# G22V5.net
KiCad netlist of a schematic drawn in EAGLE
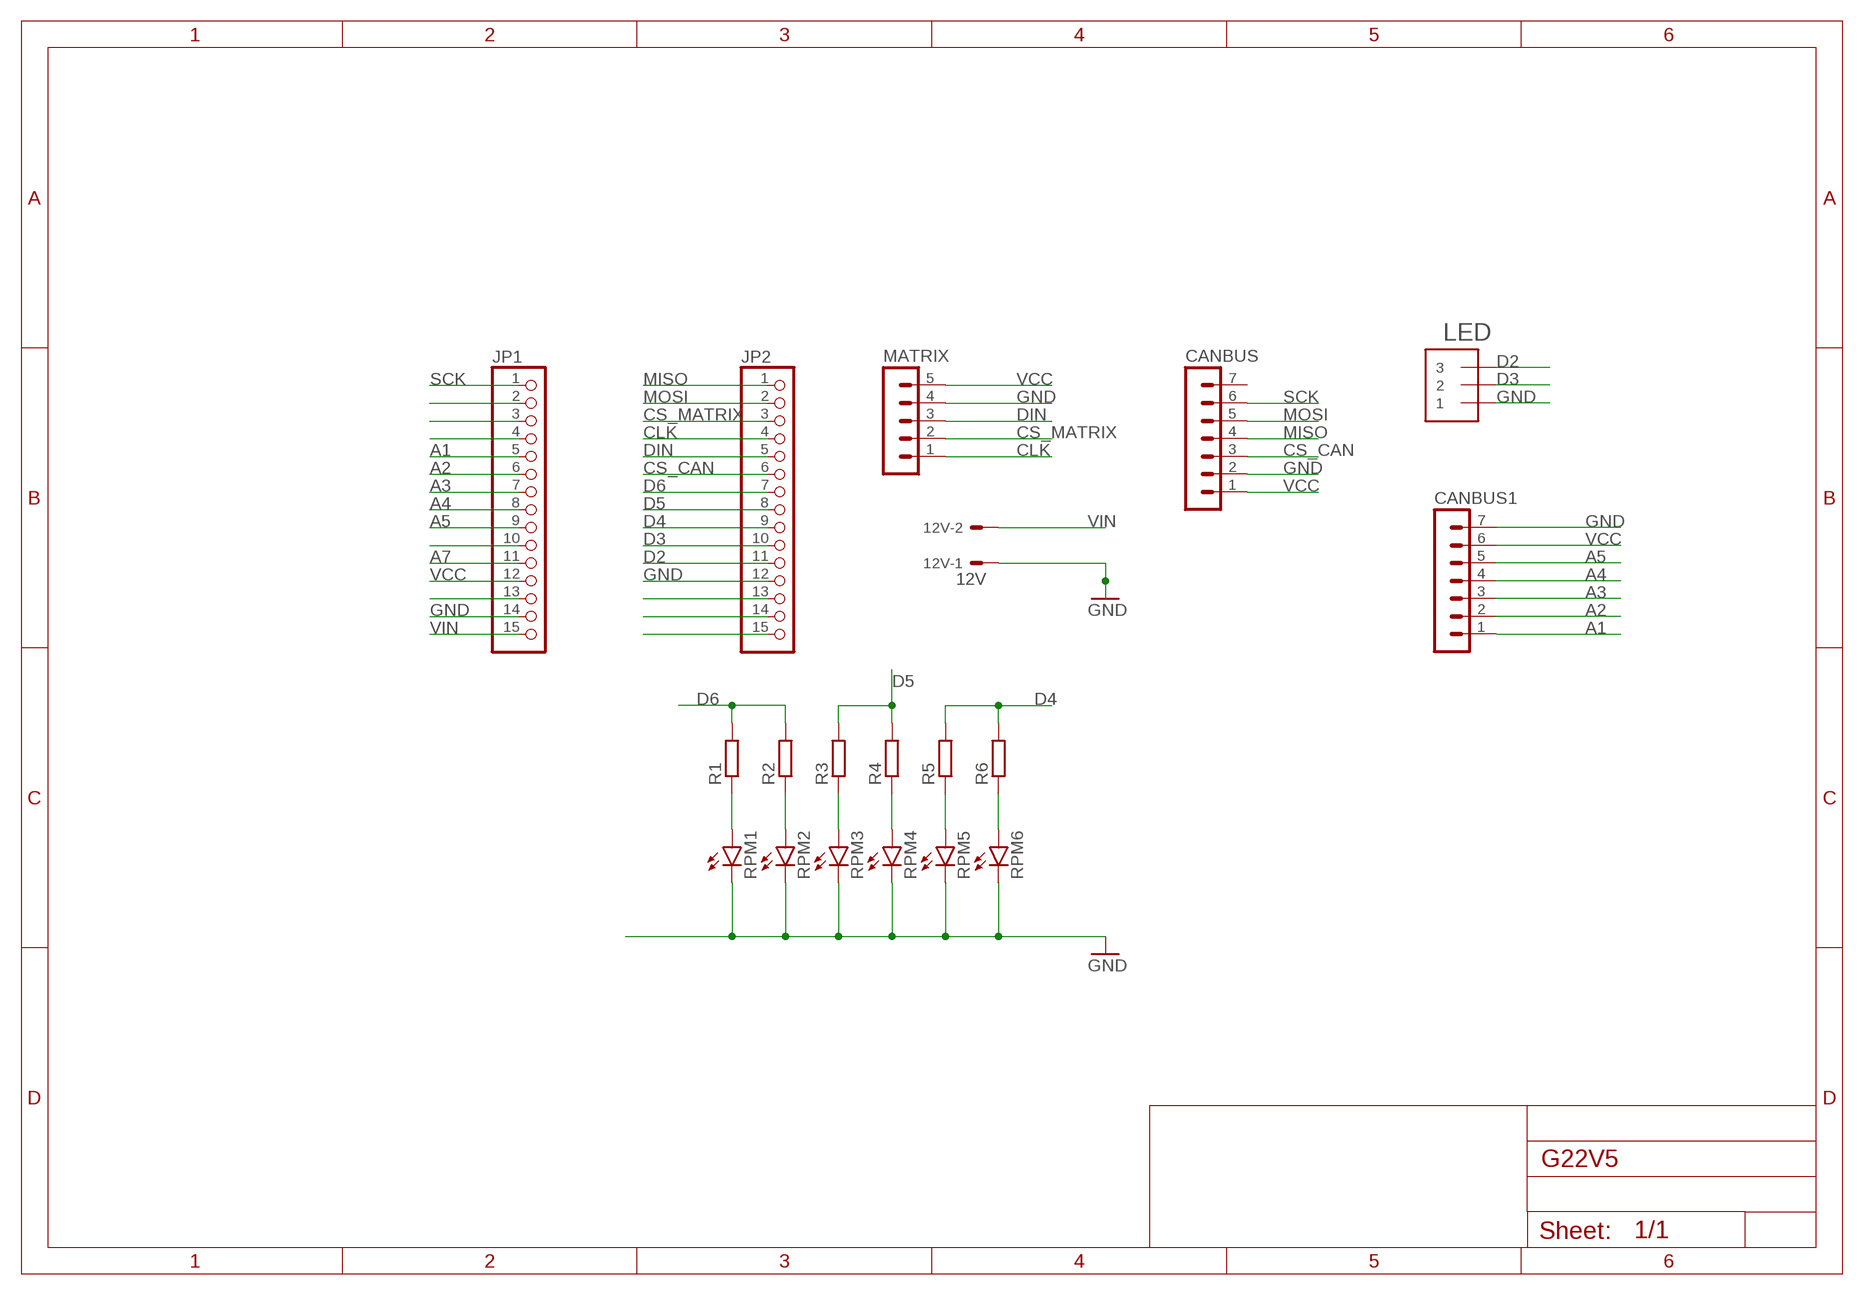
[diagram p0: schematic, sheet 1]

(export (version "E")
  (design (tool "Eeschema 10.0.6"))
  (components
    (comp (ref "12V")
      (value "12V")
      (footprint "eagle-import:22-23-2021")
      (fields (field (name "MF") "MOLEX") (field (name "MPN") "22-23-2021"))
      (libsource (lib "eagle-import") (part "22-23-2021"))
    )
    (comp (ref "CANBUS")
      (value "MA07-1")
      (footprint "eagle-import:MA07-1")
      (libsource (lib "eagle-import") (part "MA07-1"))
    )
    (comp (ref "CANBUS1")
      (value "MA07-1")
      (footprint "eagle-import:MA07-1")
      (libsource (lib "eagle-import") (part "MA07-1"))
    )
    (comp (ref "JP1")
      (value "PINHD-1X15")
      (footprint "eagle-import:1X15")
      (libsource (lib "eagle-import") (part "PINHD-1X15"))
    )
    (comp (ref "JP2")
      (value "PINHD-1X15")
      (footprint "eagle-import:1X15")
      (libsource (lib "eagle-import") (part "PINHD-1X15"))
    )
    (comp (ref "LED")
      (value "JST_ZH_3")
      (footprint "eagle-import:JST_ZH_3")
      (libsource (lib "eagle-import") (part "JST_ZH_3"))
    )
    (comp (ref "MATRIX")
      (value "MA05-1")
      (footprint "eagle-import:MA05-1")
      (libsource (lib "eagle-import") (part "MA05-1"))
    )
    (comp (ref "R1")
      (value "R-EU_M0805")
      (footprint "eagle-import:M0805")
      (libsource (lib "eagle-import") (part "R-EU_M0805"))
    )
    (comp (ref "R2")
      (value "R-EU_M0805")
      (footprint "eagle-import:M0805")
      (libsource (lib "eagle-import") (part "R-EU_M0805"))
    )
    (comp (ref "R3")
      (value "R-EU_M0805")
      (footprint "eagle-import:M0805")
      (libsource (lib "eagle-import") (part "R-EU_M0805"))
    )
    (comp (ref "R4")
      (value "R-EU_M0805")
      (footprint "eagle-import:M0805")
      (libsource (lib "eagle-import") (part "R-EU_M0805"))
    )
    (comp (ref "R5")
      (value "R-EU_M0805")
      (footprint "eagle-import:M0805")
      (libsource (lib "eagle-import") (part "R-EU_M0805"))
    )
    (comp (ref "R6")
      (value "R-EU_M0805")
      (footprint "eagle-import:M0805")
      (libsource (lib "eagle-import") (part "R-EU_M0805"))
    )
    (comp (ref "RPM1")
      (value "LED5MM")
      (footprint "eagle-import:LED5MM")
      (libsource (lib "eagle-import") (part "LED5MM"))
    )
    (comp (ref "RPM2")
      (value "LED5MM")
      (footprint "eagle-import:LED5MM")
      (libsource (lib "eagle-import") (part "LED5MM"))
    )
    (comp (ref "RPM3")
      (value "LED5MM")
      (footprint "eagle-import:LED5MM")
      (libsource (lib "eagle-import") (part "LED5MM"))
    )
    (comp (ref "RPM4")
      (value "LED5MM")
      (footprint "eagle-import:LED5MM")
      (libsource (lib "eagle-import") (part "LED5MM"))
    )
    (comp (ref "RPM5")
      (value "LED5MM")
      (footprint "eagle-import:LED5MM")
      (libsource (lib "eagle-import") (part "LED5MM"))
    )
    (comp (ref "RPM6")
      (value "LED5MM")
      (footprint "eagle-import:LED5MM")
      (libsource (lib "eagle-import") (part "LED5MM"))
    )
  )
  (nets
    (net (code "1") (name "/A1") (class "Default")
      (node (ref "CANBUS1") (pin "1") (pinfunction "1_1") (pintype "passive"))
      (node (ref "JP1") (pin "5") (pinfunction "5_5") (pintype "passive"))
    )
    (net (code "2") (name "/A2") (class "Default")
      (node (ref "CANBUS1") (pin "2") (pinfunction "2_2") (pintype "passive"))
      (node (ref "JP1") (pin "6") (pinfunction "6_6") (pintype "passive"))
    )
    (net (code "3") (name "/A3") (class "Default")
      (node (ref "CANBUS1") (pin "3") (pinfunction "3_3") (pintype "passive"))
      (node (ref "JP1") (pin "7") (pinfunction "7_7") (pintype "passive"))
    )
    (net (code "4") (name "/A4") (class "Default")
      (node (ref "CANBUS1") (pin "4") (pinfunction "4_4") (pintype "passive"))
      (node (ref "JP1") (pin "8") (pinfunction "8_8") (pintype "passive"))
    )
    (net (code "5") (name "/A5") (class "Default")
      (node (ref "CANBUS1") (pin "5") (pinfunction "5_5") (pintype "passive"))
      (node (ref "JP1") (pin "9") (pinfunction "9_9") (pintype "passive"))
    )
    (net (code "6") (name "/A7") (class "Default")
      (node (ref "JP1") (pin "11") (pinfunction "11_11") (pintype "passive"))
    )
    (net (code "7") (name "/CLK") (class "Default")
      (node (ref "JP2") (pin "4") (pinfunction "4_4") (pintype "passive"))
      (node (ref "MATRIX") (pin "1") (pinfunction "1_1") (pintype "passive"))
    )
    (net (code "8") (name "/CS_CAN") (class "Default")
      (node (ref "CANBUS") (pin "3") (pinfunction "3_3") (pintype "passive"))
      (node (ref "JP2") (pin "6") (pinfunction "6_6") (pintype "passive"))
    )
    (net (code "9") (name "/CS_MATRIX") (class "Default")
      (node (ref "JP2") (pin "3") (pinfunction "3_3") (pintype "passive"))
      (node (ref "MATRIX") (pin "2") (pinfunction "2_2") (pintype "passive"))
    )
    (net (code "10") (name "/D2") (class "Default")
      (node (ref "JP2") (pin "11") (pinfunction "11_11") (pintype "passive"))
      (node (ref "LED") (pin "P$3") (pinfunction "3_P$3") (pintype "bidirectional"))
    )
    (net (code "11") (name "/D3") (class "Default")
      (node (ref "JP2") (pin "10") (pinfunction "10_10") (pintype "passive"))
      (node (ref "LED") (pin "P$2") (pinfunction "2_P$2") (pintype "bidirectional"))
    )
    (net (code "12") (name "/D4") (class "Default")
      (node (ref "JP2") (pin "9") (pinfunction "9_9") (pintype "passive"))
      (node (ref "R5") (pin "2") (pinfunction "2_2") (pintype "passive"))
      (node (ref "R6") (pin "2") (pinfunction "2_2") (pintype "passive"))
    )
    (net (code "13") (name "/D5") (class "Default")
      (node (ref "JP2") (pin "8") (pinfunction "8_8") (pintype "passive"))
      (node (ref "R3") (pin "2") (pinfunction "2_2") (pintype "passive"))
      (node (ref "R4") (pin "2") (pinfunction "2_2") (pintype "passive"))
    )
    (net (code "14") (name "/D6") (class "Default")
      (node (ref "JP2") (pin "7") (pinfunction "7_7") (pintype "passive"))
      (node (ref "R1") (pin "2") (pinfunction "2_2") (pintype "passive"))
      (node (ref "R2") (pin "2") (pinfunction "2_2") (pintype "passive"))
    )
    (net (code "15") (name "/DIN") (class "Default")
      (node (ref "JP2") (pin "5") (pinfunction "5_5") (pintype "passive"))
      (node (ref "MATRIX") (pin "3") (pinfunction "3_3") (pintype "passive"))
    )
    (net (code "16") (name "/MISO") (class "Default")
      (node (ref "CANBUS") (pin "4") (pinfunction "4_4") (pintype "passive"))
      (node (ref "JP2") (pin "1") (pinfunction "1_1") (pintype "passive"))
    )
    (net (code "17") (name "/MOSI") (class "Default")
      (node (ref "CANBUS") (pin "5") (pinfunction "5_5") (pintype "passive"))
      (node (ref "JP2") (pin "2") (pinfunction "2_2") (pintype "passive"))
    )
    (net (code "18") (name "/SCK") (class "Default")
      (node (ref "CANBUS") (pin "6") (pinfunction "6_6") (pintype "passive"))
      (node (ref "JP1") (pin "1") (pinfunction "1_1") (pintype "passive"))
    )
    (net (code "19") (name "/VCC") (class "Default")
      (node (ref "CANBUS") (pin "1") (pinfunction "1_1") (pintype "passive"))
      (node (ref "CANBUS1") (pin "6") (pinfunction "6_6") (pintype "passive"))
      (node (ref "JP1") (pin "12") (pinfunction "12_12") (pintype "passive"))
      (node (ref "MATRIX") (pin "5") (pinfunction "5_5") (pintype "passive"))
    )
    (net (code "20") (name "/VIN") (class "Default")
      (node (ref "12V") (pin "2") (pinfunction "S_2") (pintype "passive"))
      (node (ref "JP1") (pin "15") (pinfunction "15_15") (pintype "passive"))
    )
    (net (code "21") (name "GND") (class "Default")
      (node (ref "12V") (pin "1") (pinfunction "S_1") (pintype "passive"))
      (node (ref "CANBUS") (pin "2") (pinfunction "2_2") (pintype "passive"))
      (node (ref "CANBUS1") (pin "7") (pinfunction "7_7") (pintype "passive"))
      (node (ref "JP1") (pin "14") (pinfunction "14_14") (pintype "passive"))
      (node (ref "JP2") (pin "12") (pinfunction "12_12") (pintype "passive"))
      (node (ref "LED") (pin "P$1") (pinfunction "1_P$1") (pintype "bidirectional"))
      (node (ref "MATRIX") (pin "4") (pinfunction "4_4") (pintype "passive"))
      (node (ref "RPM1") (pin "K") (pinfunction "C_K") (pintype "passive"))
      (node (ref "RPM2") (pin "K") (pinfunction "C_K") (pintype "passive"))
      (node (ref "RPM3") (pin "K") (pinfunction "C_K") (pintype "passive"))
      (node (ref "RPM4") (pin "K") (pinfunction "C_K") (pintype "passive"))
      (node (ref "RPM5") (pin "K") (pinfunction "C_K") (pintype "passive"))
      (node (ref "RPM6") (pin "K") (pinfunction "C_K") (pintype "passive"))
    )
    (net (code "22") (name "Net-(R1-Pad1)") (class "Default")
      (node (ref "R1") (pin "1") (pinfunction "1_1") (pintype "passive"))
      (node (ref "RPM1") (pin "A") (pinfunction "A_A") (pintype "passive"))
    )
    (net (code "23") (name "Net-(R2-Pad1)") (class "Default")
      (node (ref "R2") (pin "1") (pinfunction "1_1") (pintype "passive"))
      (node (ref "RPM2") (pin "A") (pinfunction "A_A") (pintype "passive"))
    )
    (net (code "24") (name "Net-(R3-Pad1)") (class "Default")
      (node (ref "R3") (pin "1") (pinfunction "1_1") (pintype "passive"))
      (node (ref "RPM3") (pin "A") (pinfunction "A_A") (pintype "passive"))
    )
    (net (code "25") (name "Net-(R4-Pad1)") (class "Default")
      (node (ref "R4") (pin "1") (pinfunction "1_1") (pintype "passive"))
      (node (ref "RPM4") (pin "A") (pinfunction "A_A") (pintype "passive"))
    )
    (net (code "26") (name "Net-(R5-Pad1)") (class "Default")
      (node (ref "R5") (pin "1") (pinfunction "1_1") (pintype "passive"))
      (node (ref "RPM5") (pin "A") (pinfunction "A_A") (pintype "passive"))
    )
    (net (code "27") (name "Net-(R6-Pad1)") (class "Default")
      (node (ref "R6") (pin "1") (pinfunction "1_1") (pintype "passive"))
      (node (ref "RPM6") (pin "A") (pinfunction "A_A") (pintype "passive"))
    )
    (net (code "28") (name "unconnected-(CANBUS-Pad7)") (class "Default")
      (node (ref "CANBUS") (pin "7") (pinfunction "7_7") (pintype "passive"))
    )
    (net (code "29") (name "unconnected-(JP1-Pad2)") (class "Default")
      (node (ref "JP1") (pin "2") (pinfunction "2_2") (pintype "passive"))
    )
    (net (code "30") (name "unconnected-(JP1-Pad3)") (class "Default")
      (node (ref "JP1") (pin "3") (pinfunction "3_3") (pintype "passive"))
    )
    (net (code "31") (name "unconnected-(JP1-Pad4)") (class "Default")
      (node (ref "JP1") (pin "4") (pinfunction "4_4") (pintype "passive"))
    )
    (net (code "32") (name "unconnected-(JP1-Pad10)") (class "Default")
      (node (ref "JP1") (pin "10") (pinfunction "10_10") (pintype "passive"))
    )
    (net (code "33") (name "unconnected-(JP1-Pad13)") (class "Default")
      (node (ref "JP1") (pin "13") (pinfunction "13_13") (pintype "passive"))
    )
    (net (code "34") (name "unconnected-(JP2-Pad13)") (class "Default")
      (node (ref "JP2") (pin "13") (pinfunction "13_13") (pintype "passive"))
    )
    (net (code "35") (name "unconnected-(JP2-Pad14)") (class "Default")
      (node (ref "JP2") (pin "14") (pinfunction "14_14") (pintype "passive"))
    )
    (net (code "36") (name "unconnected-(JP2-Pad15)") (class "Default")
      (node (ref "JP2") (pin "15") (pinfunction "15_15") (pintype "passive"))
    )
  )
)
